# Driver_Open_Collector.net
KiCad netlist of a schematic drawn in Altium Designer
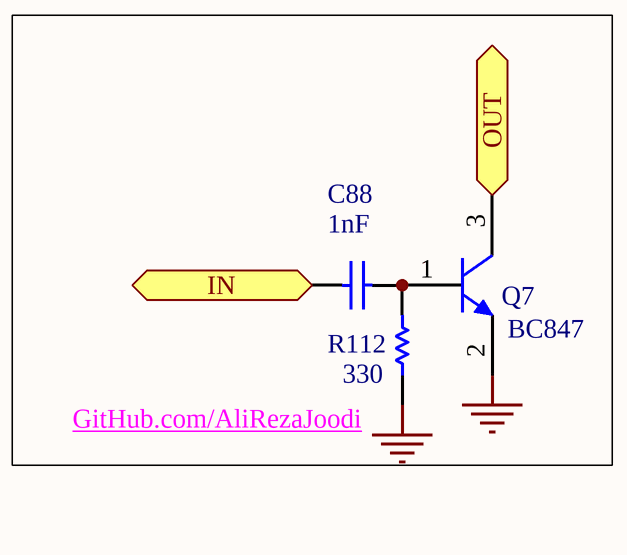
[diagram p0: Driver_Open Collector.SchDoc]

(export (version "E")
  (design (tool "Eeschema 10.0.6"))
  (components
    (comp (ref "C88")
      (value "1nF")
      (footprint "RESC3216N")
      (description "Capacitor")
      (fields (field (name "Comment") "Cap") (field (name "PUBLISHER") "Altium Limited"))
      (libsource (lib "Miscellaneous Devices") (part "Cap"))
    )
    (comp (ref "Q7")
      (value "BC847")
      (footprint "SOT23-3N")
      (description "Silicon Bipolar Transistor")
      (fields (field (name "Comment") "NPN"))
      (libsource (lib "my Libraries") (part "BC847"))
    )
    (comp (ref "R112")
      (value "330")
      (footprint "0805")
      (description "Resistor")
      (fields (field (name "Comment") "Res1") (field (name "PUBLISHER") "Altium Limited"))
      (libsource (lib "Miscellaneous Devices") (part "Res1"))
    )
  )
  (nets
    (net (code "1") (name "/IN") (class "Default")
      (node (ref "C88") (pin "1") (pinfunction "1_1") (pintype "passive"))
    )
    (net (code "2") (name "/OUT") (class "Default")
      (node (ref "Q7") (pin "3") (pinfunction "C_3") (pintype "passive"))
    )
    (net (code "3") (name "GND") (class "Default")
      (node (ref "Q7") (pin "2") (pinfunction "E_2") (pintype "passive"))
      (node (ref "R112") (pin "1") (pinfunction "1_1") (pintype "passive"))
    )
    (net (code "4") (name "Net-(Q7-B)") (class "Default")
      (node (ref "C88") (pin "2") (pinfunction "2_2") (pintype "passive"))
      (node (ref "Q7") (pin "1") (pinfunction "B_1") (pintype "passive"))
      (node (ref "R112") (pin "2") (pinfunction "2_2") (pintype "passive"))
    )
  )
)
